# 5_-_Motor_Driver_Schematic.net
KiCad netlist of a schematic drawn in Altium Designer
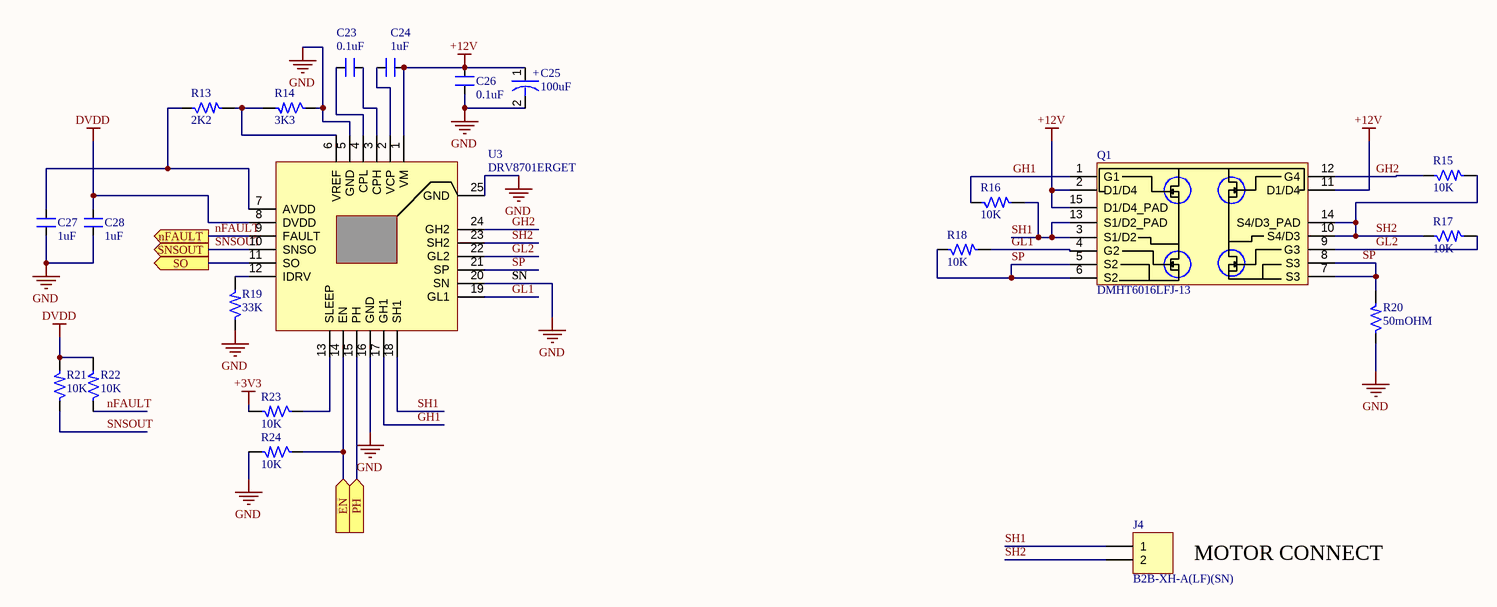
[diagram p0: [5] - Motor Driver Schematic.SchDoc]

(export (version "E")
  (design (tool "Eeschema 10.0.6"))
  (components
    (comp (ref "C23")
      (value "0.1uF")
      (footprint "CAP_0805")
      (description "0.1µF ±10% 50V Ceramic Capacitor X7R 0805 (2012 Metric)")
      (fields
        (field (name "MANUFACTURER") "Samsung")
        (field (name "MANUFACTURER PART NUMBER") "CL21B104KBCNNNC")
      )
      (libsource (lib "ESTEEMPCBLIB") (part "CAP_0.1uF-50V-10%-0805"))
    )
    (comp (ref "C24")
      (value "1uF")
      (footprint "CAP_0805")
      (description "1µF ±5% 50V Ceramic Capacitor X7R 0805 (2012 Metric)")
      (fields
        (field (name "MANUFACTURER") "Samsung")
        (field (name "MANUFACTURER PART NUMBER") "CC0805JKX7R9BB105")
      )
      (libsource (lib "ESTEEMPCBLIB") (part "CAP_1uF-50V-5%-0805"))
    )
    (comp (ref "C25")
      (value "100uF")
      (footprint "ACAP_P236_D305_H303_RAD")
      (description "100µF 25V Aluminum Electrolytic Capacitors Radial, Can - SMD 1000 Hrs @ 105°C")
      (fields
        (field (name "MANUFACTURER") "Nichicon")
        (field (name "MANUFACTURER PART NUMBER") "UWT1E101MCL1GS")
      )
      (libsource (lib "ESTEEMPCBLIB") (part "CAP-P_100uF-25V-20%-RAD"))
    )
    (comp (ref "C26")
      (value "0.1uF")
      (footprint "CAP_0805")
      (description "0.1µF ±10% 50V Ceramic Capacitor X7R 0805 (2012 Metric)")
      (fields
        (field (name "MANUFACTURER") "Samsung")
        (field (name "MANUFACTURER PART NUMBER") "CL21B104KBCNNNC")
      )
      (libsource (lib "ESTEEMPCBLIB") (part "CAP_0.1uF-50V-10%-0805"))
    )
    (comp (ref "C27")
      (value "1uF")
      (footprint "CAP_0805")
      (description "1µF ±5% 50V Ceramic Capacitor X7R 0805 (2012 Metric)")
      (fields
        (field (name "MANUFACTURER") "Samsung")
        (field (name "MANUFACTURER PART NUMBER") "CC0805JKX7R9BB105")
      )
      (libsource (lib "ESTEEMPCBLIB") (part "CAP_1uF-50V-5%-0805"))
    )
    (comp (ref "C28")
      (value "1uF")
      (footprint "CAP_0805")
      (description "1µF ±5% 50V Ceramic Capacitor X7R 0805 (2012 Metric)")
      (fields
        (field (name "MANUFACTURER") "Samsung")
        (field (name "MANUFACTURER PART NUMBER") "CC0805JKX7R9BB105")
      )
      (libsource (lib "ESTEEMPCBLIB") (part "CAP_1uF-50V-5%-0805"))
    )
    (comp (ref "J4")
      (value "B2B-XH-A(LF)(SN)")
      (footprint "CON2_100_B2B-XH-A_TH_ST")
      (description "2 Pins, 1 Row 2.54mm Pitch, Straight Connector, male")
      (fields (field (name "MANUFACTURER") "JST") (field (name "MATING PART NUMBER") "XHP-2"))
      (libsource (lib "ESTEEMPCBLIB") (part "CON-PLG_2X1-100-ST-TH"))
    )
    (comp (ref "Q1")
      (value "DMHT6016LFJ-13")
      (footprint "DFN5045-12_33_212_27X15_SMD_1")
      (description "Mosfet Array 4 N-Channel 14.8A (Ta) Surface Mount V-DFN5045-12")
      (fields (field (name "MANUFACTURER") "ON Semiconductor"))
      (libsource (lib "ESTEEMPCBLIB") (part "MOSFET-N_60V-14.8A-V-DFN5045-12"))
    )
    (comp (ref "R13")
      (value "2K2")
      (footprint "RES_0603")
      (description "2.2 kOhms ±5% 0.1W, 1/10W Chip Resistor 0603 (1608 Metric) Automotive AEC-Q200 Thick Film")
      (fields
        (field (name "MANUFACTURER") "Stackpole Electronics")
        (field (name "MANUFACTURER PART NUMBER") "ERJ-3GEYJ222V")
      )
      (libsource (lib "ESTEEMPCBLIB") (part "RES_2K2-0.1W-5%-0603"))
    )
    (comp (ref "R14")
      (value "3K3")
      (footprint "RES_0603")
      (description "3.3 kOhms ±1% 0.1W, 1/10W Chip Resistor 0603 (1608 Metric) Automotive AEC-Q200 Thick Film")
      (fields (field (name "MANUFACTURER") "Wilson") (field (name "MANUFACTURER PART NUMBER") "WR06X3301FTL"))
      (libsource (lib "ESTEEMPCBLIB") (part "RES_3.3K-0.1W-1%-0603"))
    )
    (comp (ref "R15")
      (value "10K")
      (footprint "RES_0603")
      (description "10 kOhms ±1% 0.1W, 1/10W Chip Resistor 0603 (1608 Metric) Automotive AEC-Q200 Thick Film")
      (fields (field (name "MANUFACTURER") "Walsin") (field (name "MANUFACTURER PART NUMBER") "WR06X1002FTL"))
      (libsource (lib "ESTEEMPCBLIB") (part "RES_10K-0.1W-1%-0603"))
    )
    (comp (ref "R16")
      (value "10K")
      (footprint "RES_0603")
      (description "10 kOhms ±1% 0.1W, 1/10W Chip Resistor 0603 (1608 Metric) Automotive AEC-Q200 Thick Film")
      (fields (field (name "MANUFACTURER") "Walsin") (field (name "MANUFACTURER PART NUMBER") "WR06X1002FTL"))
      (libsource (lib "ESTEEMPCBLIB") (part "RES_10K-0.1W-1%-0603"))
    )
    (comp (ref "R17")
      (value "10K")
      (footprint "RES_0603")
      (description "10 kOhms ±1% 0.1W, 1/10W Chip Resistor 0603 (1608 Metric) Automotive AEC-Q200 Thick Film")
      (fields (field (name "MANUFACTURER") "Walsin") (field (name "MANUFACTURER PART NUMBER") "WR06X1002FTL"))
      (libsource (lib "ESTEEMPCBLIB") (part "RES_10K-0.1W-1%-0603"))
    )
    (comp (ref "R18")
      (value "10K")
      (footprint "RES_0603")
      (description "10 kOhms ±1% 0.1W, 1/10W Chip Resistor 0603 (1608 Metric) Automotive AEC-Q200 Thick Film")
      (fields (field (name "MANUFACTURER") "Walsin") (field (name "MANUFACTURER PART NUMBER") "WR06X1002FTL"))
      (libsource (lib "ESTEEMPCBLIB") (part "RES_10K-0.1W-1%-0603"))
    )
    (comp (ref "R19")
      (value "33K")
      (footprint "RES_0805")
      (fields
        (field (name "MANUFACTURER") "Vishay BCcomponents")
        (field (name "MANUFACTURER PART NUMBER") "CRG0805F33K")
      )
      (libsource (lib "ESTEEMPCBLIB") (part "RES_33K-0.125W-1%-0805"))
    )
    (comp (ref "R20")
      (value "50mOHM")
      (footprint "RES_2512")
      (fields
        (field (name "MANUFACTURER") "Yageo")
        (field (name "MANUFACTURER PART NUMBER") "PA2512FKF7W0R05E")
      )
      (libsource (lib "ESTEEMPCBLIB") (part "RES_50mOhm-2W-1%-2512"))
    )
    (comp (ref "R21")
      (value "10K")
      (footprint "RES_0603")
      (description "10 kOhms ±1% 0.1W, 1/10W Chip Resistor 0603 (1608 Metric) Automotive AEC-Q200 Thick Film")
      (fields (field (name "MANUFACTURER") "Walsin") (field (name "MANUFACTURER PART NUMBER") "WR06X1002FTL"))
      (libsource (lib "ESTEEMPCBLIB") (part "RES_10K-0.1W-1%-0603"))
    )
    (comp (ref "R22")
      (value "10K")
      (footprint "RES_0603")
      (description "10 kOhms ±1% 0.1W, 1/10W Chip Resistor 0603 (1608 Metric) Automotive AEC-Q200 Thick Film")
      (fields (field (name "MANUFACTURER") "Walsin") (field (name "MANUFACTURER PART NUMBER") "WR06X1002FTL"))
      (libsource (lib "ESTEEMPCBLIB") (part "RES_10K-0.1W-1%-0603"))
    )
    (comp (ref "R23")
      (value "10K")
      (footprint "RES_0603")
      (description "10 kOhms ±1% 0.1W, 1/10W Chip Resistor 0603 (1608 Metric) Automotive AEC-Q200 Thick Film")
      (fields (field (name "MANUFACTURER") "Walsin") (field (name "MANUFACTURER PART NUMBER") "WR06X1002FTL"))
      (libsource (lib "ESTEEMPCBLIB") (part "RES_10K-0.1W-1%-0603"))
    )
    (comp (ref "R24")
      (value "10K")
      (footprint "RES_0603")
      (description "10 kOhms ±1% 0.1W, 1/10W Chip Resistor 0603 (1608 Metric) Automotive AEC-Q200 Thick Film")
      (fields (field (name "MANUFACTURER") "Walsin") (field (name "MANUFACTURER PART NUMBER") "WR06X1002FTL"))
      (libsource (lib "ESTEEMPCBLIB") (part "RES_10K-0.1W-1%-0603"))
    )
    (comp (ref "U3")
      (value "DRV8701ERGET")
      (footprint "VFQFN24_19.6_196_12X32_SMD_1")
      (description "Motor Driver Power MOSFET Parallel 24-VQFN (4x4)")
      (fields (field (name "MANUFACTURER") "Texas Instruments"))
      (libsource (lib "ESTEEMPCBLIB") (part "IC_DRV8701ERGET"))
    )
  )
  (nets
    (net (code "1") (name "+3V3") (class "Default")
      (node (ref "R23") (pin "2") (pinfunction "2_2") (pintype "passive"))
    )
    (net (code "2") (name "+12V") (class "Default")
      (node (ref "C24") (pin "1") (pinfunction "1_1") (pintype "passive"))
      (node (ref "C25") (pin "1") (pinfunction "1_1") (pintype "passive"))
      (node (ref "C26") (pin "2") (pinfunction "2_2") (pintype "passive"))
      (node (ref "Q1") (pin "11") (pinfunction "D1/D4_11") (pintype "passive"))
      (node (ref "Q1") (pin "15") (pinfunction "D1/D4_PAD_15") (pintype "passive"))
      (node (ref "Q1") (pin "2") (pinfunction "D1/D4_2") (pintype "passive"))
      (node (ref "U3") (pin "1") (pinfunction "VM_1") (pintype "passive"))
    )
    (net (code "3") (name "/EN") (class "Default")
      (node (ref "R24") (pin "1") (pinfunction "1_1") (pintype "passive"))
      (node (ref "U3") (pin "14") (pinfunction "EN_14") (pintype "passive"))
    )
    (net (code "4") (name "/GH1") (class "Default")
      (node (ref "Q1") (pin "1") (pinfunction "G1_1") (pintype "passive"))
      (node (ref "R16") (pin "1") (pinfunction "1_1") (pintype "passive"))
      (node (ref "U3") (pin "17") (pinfunction "GH1_17") (pintype "passive"))
    )
    (net (code "5") (name "/GH2") (class "Default")
      (node (ref "Q1") (pin "12") (pinfunction "G4_12") (pintype "passive"))
      (node (ref "R15") (pin "1") (pinfunction "1_1") (pintype "passive"))
      (node (ref "U3") (pin "24") (pinfunction "GH2_24") (pintype "passive"))
    )
    (net (code "6") (name "/GL1") (class "Default")
      (node (ref "Q1") (pin "4") (pinfunction "G2_4") (pintype "passive"))
      (node (ref "R18") (pin "2") (pinfunction "2_2") (pintype "passive"))
      (node (ref "U3") (pin "19") (pinfunction "GL1_19") (pintype "passive"))
    )
    (net (code "7") (name "/GL2") (class "Default")
      (node (ref "Q1") (pin "9") (pinfunction "G3_9") (pintype "passive"))
      (node (ref "R17") (pin "2") (pinfunction "2_2") (pintype "passive"))
      (node (ref "U3") (pin "22") (pinfunction "GL2_22") (pintype "passive"))
    )
    (net (code "8") (name "/PH") (class "Default")
      (node (ref "U3") (pin "15") (pinfunction "PH_15") (pintype "passive"))
    )
    (net (code "9") (name "/SH1") (class "Default")
      (node (ref "J4") (pin "1") (pinfunction "1_1") (pintype "passive"))
      (node (ref "Q1") (pin "13") (pinfunction "S1/D2_PAD_13") (pintype "passive"))
      (node (ref "Q1") (pin "3") (pinfunction "S1/D2_3") (pintype "passive"))
      (node (ref "R16") (pin "2") (pinfunction "2_2") (pintype "passive"))
      (node (ref "U3") (pin "18") (pinfunction "SH1_18") (pintype "passive"))
    )
    (net (code "10") (name "/SH2") (class "Default")
      (node (ref "J4") (pin "2") (pinfunction "2_2") (pintype "passive"))
      (node (ref "Q1") (pin "10") (pinfunction "S4/D3_10") (pintype "passive"))
      (node (ref "Q1") (pin "14") (pinfunction "S4/D3_PAD_14") (pintype "passive"))
      (node (ref "R15") (pin "2") (pinfunction "2_2") (pintype "passive"))
      (node (ref "R17") (pin "1") (pinfunction "1_1") (pintype "passive"))
      (node (ref "U3") (pin "23") (pinfunction "SH2_23") (pintype "passive"))
    )
    (net (code "11") (name "/SNSOUT") (class "Default")
      (node (ref "R21") (pin "1") (pinfunction "1_1") (pintype "passive"))
      (node (ref "U3") (pin "10") (pinfunction "SNSO_10") (pintype "passive"))
    )
    (net (code "12") (name "/SO") (class "Default")
      (node (ref "U3") (pin "11") (pinfunction "SO_11") (pintype "passive"))
    )
    (net (code "13") (name "/SP") (class "Default")
      (node (ref "Q1") (pin "5") (pinfunction "S2_5") (pintype "passive"))
      (node (ref "Q1") (pin "6") (pinfunction "S2_6") (pintype "passive"))
      (node (ref "Q1") (pin "7") (pinfunction "S3_7") (pintype "passive"))
      (node (ref "Q1") (pin "8") (pinfunction "S3_8") (pintype "passive"))
      (node (ref "R18") (pin "1") (pinfunction "1_1") (pintype "passive"))
      (node (ref "R20") (pin "2") (pinfunction "2_2") (pintype "passive"))
      (node (ref "U3") (pin "21") (pinfunction "SP_21") (pintype "passive"))
    )
    (net (code "14") (name "/nFAULT") (class "Default")
      (node (ref "R22") (pin "1") (pinfunction "1_1") (pintype "passive"))
      (node (ref "U3") (pin "9") (pinfunction "FAULT_9") (pintype "passive"))
    )
    (net (code "15") (name "DVDD") (class "Default")
      (node (ref "C28") (pin "2") (pinfunction "2_2") (pintype "passive"))
      (node (ref "R21") (pin "2") (pinfunction "2_2") (pintype "passive"))
      (node (ref "R22") (pin "2") (pinfunction "2_2") (pintype "passive"))
      (node (ref "U3") (pin "8") (pinfunction "DVDD_8") (pintype "passive"))
    )
    (net (code "16") (name "GND") (class "Default")
      (node (ref "C25") (pin "2") (pinfunction "2_2") (pintype "passive"))
      (node (ref "C26") (pin "1") (pinfunction "1_1") (pintype "passive"))
      (node (ref "C27") (pin "1") (pinfunction "1_1") (pintype "passive"))
      (node (ref "C28") (pin "1") (pinfunction "1_1") (pintype "passive"))
      (node (ref "R14") (pin "1") (pinfunction "1_1") (pintype "passive"))
      (node (ref "R19") (pin "1") (pinfunction "1_1") (pintype "passive"))
      (node (ref "R20") (pin "1") (pinfunction "1_1") (pintype "passive"))
      (node (ref "R24") (pin "2") (pinfunction "2_2") (pintype "passive"))
      (node (ref "U3") (pin "16") (pinfunction "GND_16") (pintype "passive"))
      (node (ref "U3") (pin "20") (pinfunction "SN_20") (pintype "passive"))
      (node (ref "U3") (pin "25") (pinfunction "GND_25") (pintype "passive"))
      (node (ref "U3") (pin "5") (pinfunction "GND_5") (pintype "passive"))
    )
    (net (code "17") (name "Net-(U3-AVDD)") (class "Default")
      (node (ref "C27") (pin "2") (pinfunction "2_2") (pintype "passive"))
      (node (ref "R13") (pin "1") (pinfunction "1_1") (pintype "passive"))
      (node (ref "U3") (pin "7") (pinfunction "AVDD_7") (pintype "passive"))
    )
    (net (code "18") (name "Net-(U3-CPH)") (class "Default")
      (node (ref "C23") (pin "1") (pinfunction "1_1") (pintype "passive"))
      (node (ref "U3") (pin "3") (pinfunction "CPH_3") (pintype "passive"))
    )
    (net (code "19") (name "Net-(U3-CPL)") (class "Default")
      (node (ref "C23") (pin "2") (pinfunction "2_2") (pintype "passive"))
      (node (ref "U3") (pin "4") (pinfunction "CPL_4") (pintype "passive"))
    )
    (net (code "20") (name "Net-(U3-IDRV)") (class "Default")
      (node (ref "R19") (pin "2") (pinfunction "2_2") (pintype "passive"))
      (node (ref "U3") (pin "12") (pinfunction "IDRV_12") (pintype "passive"))
    )
    (net (code "21") (name "Net-(U3-SLEEP)") (class "Default")
      (node (ref "R23") (pin "1") (pinfunction "1_1") (pintype "passive"))
      (node (ref "U3") (pin "13") (pinfunction "SLEEP_13") (pintype "passive"))
    )
    (net (code "22") (name "Net-(U3-VCP)") (class "Default")
      (node (ref "C24") (pin "2") (pinfunction "2_2") (pintype "passive"))
      (node (ref "U3") (pin "2") (pinfunction "VCP_2") (pintype "passive"))
    )
    (net (code "23") (name "Net-(U3-VREF)") (class "Default")
      (node (ref "R13") (pin "2") (pinfunction "2_2") (pintype "passive"))
      (node (ref "R14") (pin "2") (pinfunction "2_2") (pintype "passive"))
      (node (ref "U3") (pin "6") (pinfunction "VREF_6") (pintype "passive"))
    )
  )
)
